# WIFI_Module.net
KiCad netlist of a schematic drawn in Altium Designer
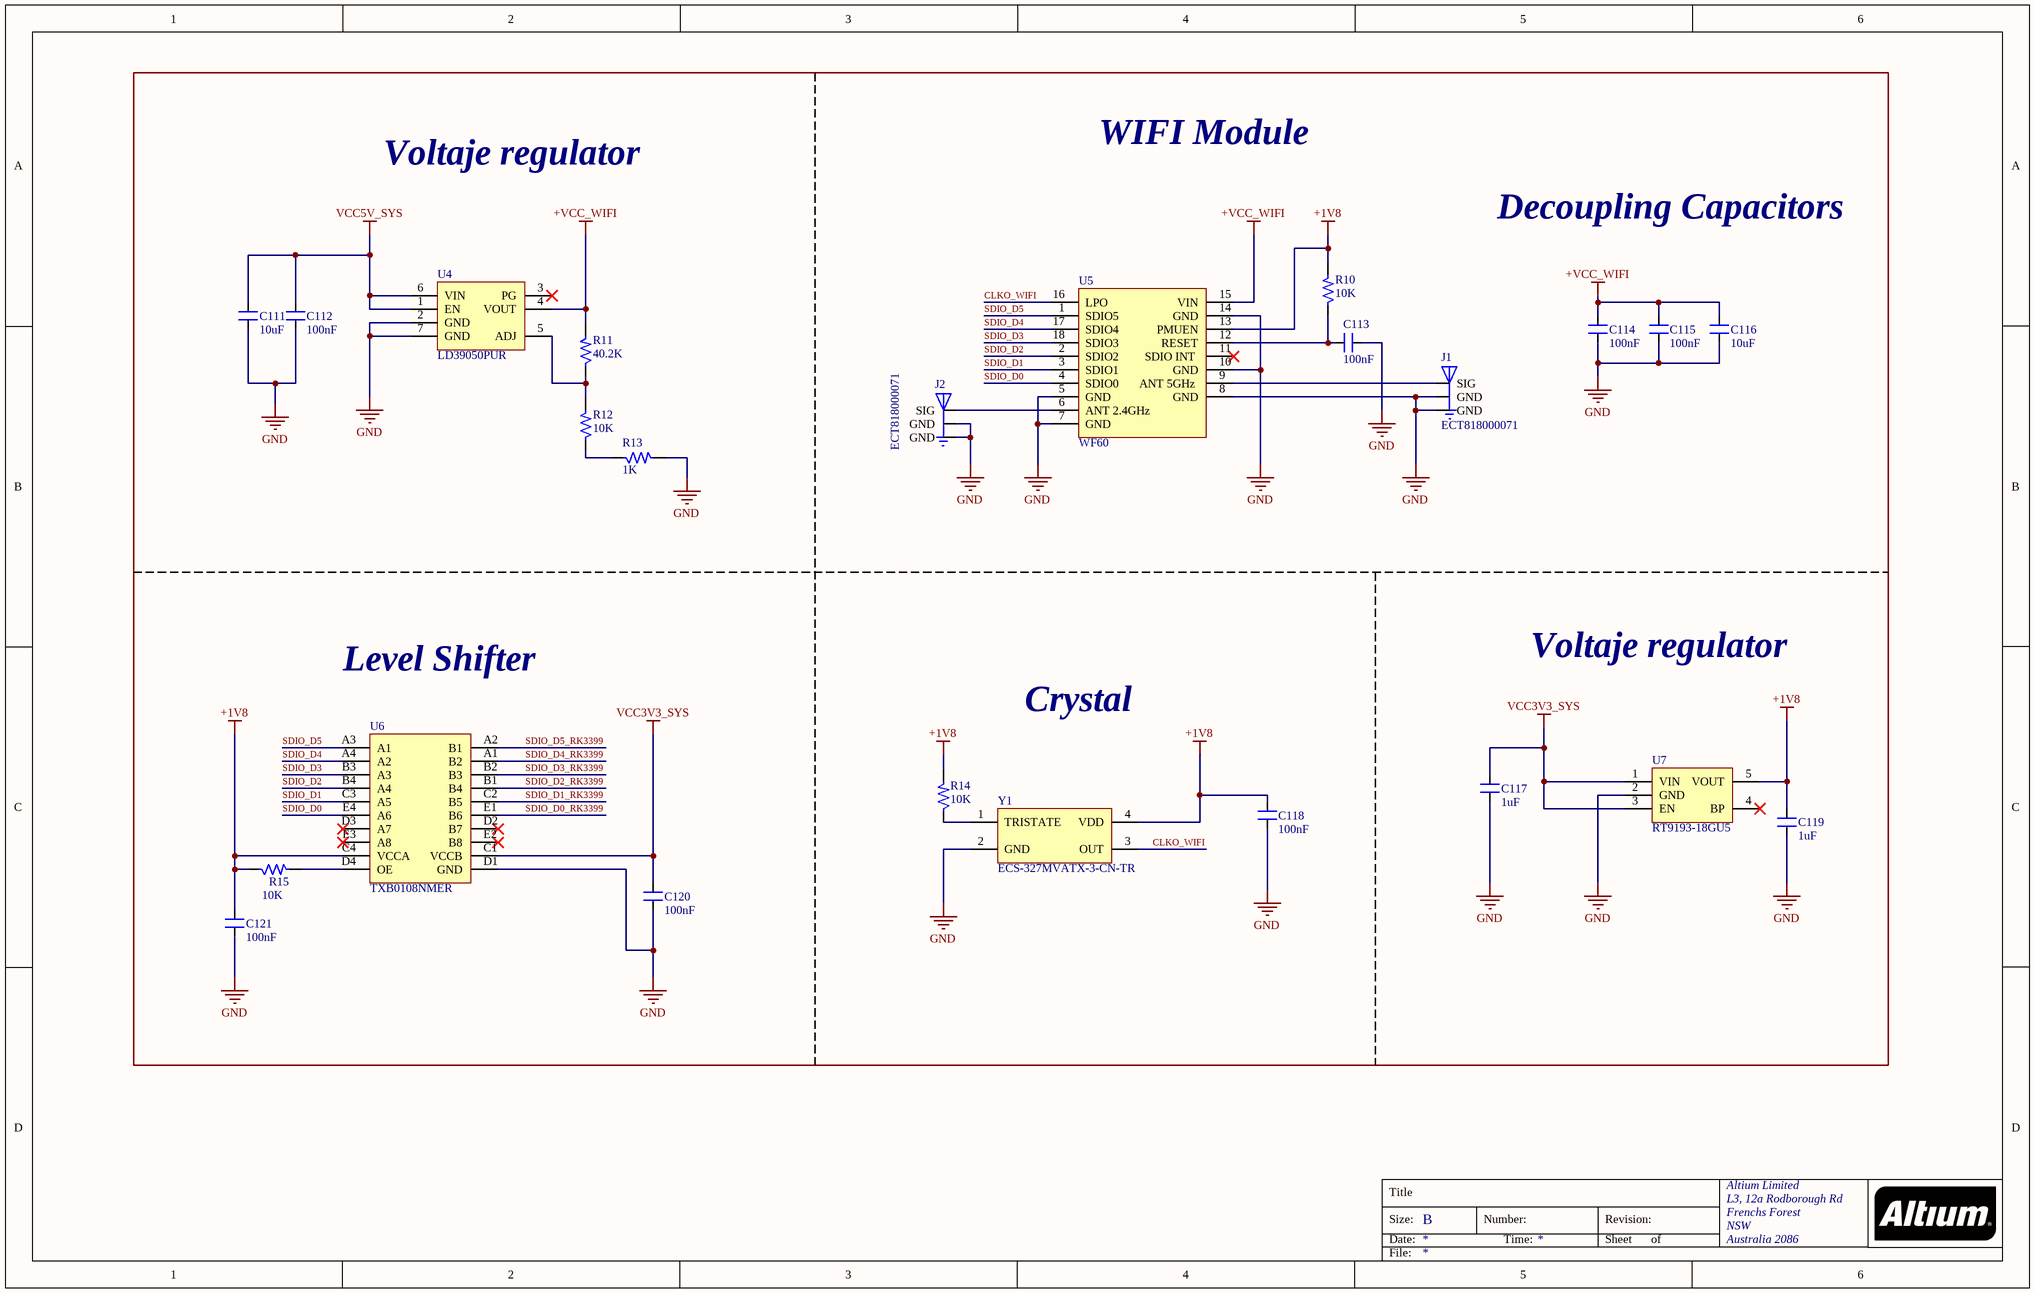
[diagram p0: WIFI_Module.SchDoc]

(export (version "E")
  (design (tool "Eeschema 10.0.6"))
  (components
    (comp (ref "C111")
      (value "10uF")
      (footprint "CAP_0603")
      (description "10µF ±10% 25V Ceramic Capacitor X5R 0603 (1608 Metric)")
      (fields
        (field (name "MANUFACTURER") "Murata Electronics")
        (field (name "MANUFACTURER PART NUMBER") "GRM188R61E106KA73D")
      )
      (libsource (lib "EsteemPCB_SOM_Course_intlib") (part "CAP_10uF-25V-10%-0603"))
    )
    (comp (ref "C112")
      (value "100nF")
      (footprint "CAP_0201")
      (description "0.1µF ±10% 25V Ceramic Capacitor X5R 0201 (0603 Metric)")
      (fields
        (field (name "MANUFACTURER") "TDK Corporation")
        (field (name "MANUFACTURER PART NUMBER") "C0603X5R1E104K030BB")
      )
      (libsource (lib "EsteemPCB_SOM_Course_intlib") (part "CAP_100nF-25V-10%-0201"))
    )
    (comp (ref "C113")
      (value "100nF")
      (footprint "CAP_0201")
      (description "0.1µF ±10% 25V Ceramic Capacitor X5R 0201 (0603 Metric)")
      (fields
        (field (name "MANUFACTURER") "TDK Corporation")
        (field (name "MANUFACTURER PART NUMBER") "C0603X5R1E104K030BB")
      )
      (libsource (lib "EsteemPCB_SOM_Course_intlib") (part "CAP_100nF-25V-10%-0201"))
    )
    (comp (ref "C114")
      (value "100nF")
      (footprint "CAP_0201")
      (description "0.1µF ±10% 25V Ceramic Capacitor X5R 0201 (0603 Metric)")
      (fields
        (field (name "MANUFACTURER") "TDK Corporation")
        (field (name "MANUFACTURER PART NUMBER") "C0603X5R1E104K030BB")
      )
      (libsource (lib "EsteemPCB_SOM_Course_intlib") (part "CAP_100nF-25V-10%-0201"))
    )
    (comp (ref "C115")
      (value "100nF")
      (footprint "CAP_0201")
      (description "0.1µF ±10% 25V Ceramic Capacitor X5R 0201 (0603 Metric)")
      (fields
        (field (name "MANUFACTURER") "TDK Corporation")
        (field (name "MANUFACTURER PART NUMBER") "C0603X5R1E104K030BB")
      )
      (libsource (lib "EsteemPCB_SOM_Course_intlib") (part "CAP_100nF-25V-10%-0201"))
    )
    (comp (ref "C116")
      (value "10uF")
      (footprint "CAP_0603")
      (description "10µF ±10% 25V Ceramic Capacitor X5R 0603 (1608 Metric)")
      (fields
        (field (name "MANUFACTURER") "Murata Electronics")
        (field (name "MANUFACTURER PART NUMBER") "GRM188R61E106KA73D")
      )
      (libsource (lib "EsteemPCB_SOM_Course_intlib") (part "CAP_10uF-25V-10%-0603"))
    )
    (comp (ref "C117")
      (value "1uF")
      (footprint "CAP_0201")
      (description "1µF ±20% 16V Ceramic Capacitor X5R 0201 (0603 Metric)")
      (fields
        (field (name "MANUFACTURER") "Samsung Electro-Mechanics")
        (field (name "MANUFACTURER PART NUMBER") "CL03A105MO3NRNH")
      )
      (libsource (lib "EsteemPCB_SOM_Course_intlib") (part "CAP_1uF-16V-10%-0201"))
    )
    (comp (ref "C118")
      (value "100nF")
      (footprint "CAP_0201")
      (description "0.1µF ±10% 25V Ceramic Capacitor X5R 0201 (0603 Metric)")
      (fields
        (field (name "MANUFACTURER") "TDK Corporation")
        (field (name "MANUFACTURER PART NUMBER") "C0603X5R1E104K030BB")
      )
      (libsource (lib "EsteemPCB_SOM_Course_intlib") (part "CAP_100nF-25V-10%-0201"))
    )
    (comp (ref "C119")
      (value "1uF")
      (footprint "CAP_0201")
      (description "1µF ±20% 16V Ceramic Capacitor X5R 0201 (0603 Metric)")
      (fields
        (field (name "MANUFACTURER") "Samsung Electro-Mechanics")
        (field (name "MANUFACTURER PART NUMBER") "CL03A105MO3NRNH")
      )
      (libsource (lib "EsteemPCB_SOM_Course_intlib") (part "CAP_1uF-16V-10%-0201"))
    )
    (comp (ref "C120")
      (value "100nF")
      (footprint "CAP_0201")
      (description "0.1µF ±10% 25V Ceramic Capacitor X5R 0201 (0603 Metric)")
      (fields
        (field (name "MANUFACTURER") "TDK Corporation")
        (field (name "MANUFACTURER PART NUMBER") "C0603X5R1E104K030BB")
      )
      (libsource (lib "EsteemPCB_SOM_Course_intlib") (part "CAP_100nF-25V-10%-0201"))
    )
    (comp (ref "C121")
      (value "100nF")
      (footprint "CAP_0201")
      (description "0.1µF ±10% 25V Ceramic Capacitor X5R 0201 (0603 Metric)")
      (fields
        (field (name "MANUFACTURER") "TDK Corporation")
        (field (name "MANUFACTURER PART NUMBER") "C0603X5R1E104K030BB")
      )
      (libsource (lib "EsteemPCB_SOM_Course_intlib") (part "CAP_100nF-25V-10%-0201"))
    )
    (comp (ref "J1")
      (value "ECT818000071")
      (footprint "CON3_UFL_116_SMD_ST")
      (description "SMD RF Connectors/Coaxial Connectors RoHS")
      (fields (field (name "MANUFACTURER") "ECT"))
      (libsource (lib "EsteemPCB_SOM_Course_intlib") (part "CON-PLG_3X1-ECT818000071-ST-SMD"))
    )
    (comp (ref "J2")
      (value "ECT818000071")
      (footprint "CON3_UFL_116_SMD_ST")
      (description "SMD RF Connectors/Coaxial Connectors RoHS")
      (fields (field (name "MANUFACTURER") "ECT"))
      (libsource (lib "EsteemPCB_SOM_Course_intlib") (part "CON-PLG_3X1-ECT818000071-ST-SMD"))
    )
    (comp (ref "R10")
      (value "10K")
      (footprint "RES_0201")
      (description "10 kOhms ±1% 0.05W, 1/20W Chip Resistor 0201 (0603 Metric) Thick Film")
      (fields
        (field (name "MANUFACTURER") "Stackpole Electronics Inc")
        (field (name "MANUFACTURER PART NUMBER") "RMCF0201FT10K0")
      )
      (libsource (lib "EsteemPCB_SOM_Course_intlib") (part "RES_10K-0.05W-1%-0201"))
    )
    (comp (ref "R11")
      (value "40.2K")
      (footprint "RES_0201")
      (fields
        (field (name "MANUFACTURER") "Yageo")
        (field (name "MANUFACTURER PART NUMBER") "AC0201FR-0740K2L")
      )
      (libsource (lib "EsteemPCB_SOM_Course_intlib") (part "RES_40.2K-0.05W-1%-0201"))
    )
    (comp (ref "R12")
      (value "10K")
      (footprint "RES_0201")
      (description "10 kOhms ±1% 0.05W, 1/20W Chip Resistor 0201 (0603 Metric) Thick Film")
      (fields
        (field (name "MANUFACTURER") "Stackpole Electronics Inc")
        (field (name "MANUFACTURER PART NUMBER") "RMCF0201FT10K0")
      )
      (libsource (lib "EsteemPCB_SOM_Course_intlib") (part "RES_10K-0.05W-1%-0201"))
    )
    (comp (ref "R13")
      (value "1K")
      (footprint "RES_0402")
      (description "1 kOhms ±1% 0.1W, 1/10W Chip Resistor 0402 (1005 Metric) Anti-Sulfur Thin Film")
      (fields
        (field (name "MANUFACTURER") "Vishay Beyschlag/Draloric/BC Components")
        (field (name "MANUFACTURER PART NUMBER") "MCS04020C1001FE000")
      )
      (libsource (lib "EsteemPCB_SOM_Course_intlib") (part "RES_1K-0.1W-1%-0402"))
    )
    (comp (ref "R14")
      (value "10K")
      (footprint "RES_0201")
      (description "10 kOhms ±1% 0.05W, 1/20W Chip Resistor 0201 (0603 Metric) Thick Film")
      (fields
        (field (name "MANUFACTURER") "Stackpole Electronics Inc")
        (field (name "MANUFACTURER PART NUMBER") "RMCF0201FT10K0")
      )
      (libsource (lib "EsteemPCB_SOM_Course_intlib") (part "RES_10K-0.05W-1%-0201"))
    )
    (comp (ref "R15")
      (value "10K")
      (footprint "RES_0201")
      (description "10 kOhms ±1% 0.05W, 1/20W Chip Resistor 0201 (0603 Metric) Thick Film")
      (fields
        (field (name "MANUFACTURER") "Stackpole Electronics Inc")
        (field (name "MANUFACTURER PART NUMBER") "RMCF0201FT10K0")
      )
      (libsource (lib "EsteemPCB_SOM_Course_intlib") (part "RES_10K-0.05W-1%-0201"))
    )
    (comp (ref "U4")
      (value "LD39050PUR")
      (footprint "DFN-6_37.4_165_33X15_SMD")
      (description "Adjustable 5.5V 0.8V 500mA DFN-6 Linear Voltage Regulators RoHS")
      (fields (field (name "MANUFACTURER") "STMicroelectronics"))
      (libsource (lib "EsteemPCB_SOM_Course_intlib") (part "REG_5.5V-0~5.1V-0.5A-2.55W-DFN-6"))
    )
    (comp (ref "U5")
      (value "WF60")
      (footprint "MOD_WF60")
      (description "Amp’ed RF Tech presents the WF60 WiFi dual\r\nband module: 802.11abgn.")
      (fields (field (name "MANUFACTURER") "Amp’ed"))
      (libsource (lib "EsteemPCB_SOM_Course_intlib") (part "MOD_WF60-SMD"))
    )
    (comp (ref "U6")
      (value "TXB0108NMER")
      (footprint "NFBGA_31.4_125.9X102.36")
      (fields (field (name "MANUFACTURER") "Texas Instruments"))
      (libsource (lib "EsteemPCB_SOM_Course_intlib") (part "IC_TXB0108NMER"))
    )
    (comp (ref "U7")
      (value "RT9193-18GU5")
      (footprint "SC70-5")
      (description "Linear Voltage Regulator IC 1 Output 300mA SC-70-5")
      (fields (field (name "MANUFACTURER") "Richtek USA Inc."))
      (libsource (lib "EsteemPCB_SOM_Course_intlib") (part "REG_1.8V-300mA-5.5V-SC70-5"))
    )
    (comp (ref "Y1")
      (value "ECS-327MVATX-3-CN-TR")
      (footprint "XTAL_57_35X31_SMD")
      (description "32.768kHz XO (Standard) CMOS Oscillator 1.6V ~ 3.6V Enable/Disable 4-SMD, No Lead")
      (fields (field (name "MANUFACTURER") "ECS INC"))
      (libsource (lib "EsteemPCB_SOM_Course_intlib") (part "XTAL_ECS-327MVATX-2-CN-TR"))
    )
  )
  (nets
    (net (code "1") (name "+1V8") (class "Default")
      (node (ref "C118") (pin "2") (pinfunction "2_2") (pintype "passive"))
      (node (ref "C119") (pin "2") (pinfunction "2_2") (pintype "passive"))
      (node (ref "C121") (pin "2") (pinfunction "2_2") (pintype "passive"))
      (node (ref "R10") (pin "2") (pinfunction "2_2") (pintype "passive"))
      (node (ref "R14") (pin "2") (pinfunction "2_2") (pintype "passive"))
      (node (ref "R15") (pin "1") (pinfunction "1_1") (pintype "passive"))
      (node (ref "U5") (pin "13") (pinfunction "PMUEN_13") (pintype "passive"))
      (node (ref "U6") (pin "C4") (pinfunction "VCCA_C4") (pintype "passive"))
      (node (ref "U7") (pin "5") (pinfunction "VOUT_5") (pintype "passive"))
      (node (ref "Y1") (pin "4") (pinfunction "VDD_4") (pintype "passive"))
    )
    (net (code "2") (name "+VCC_WIFI") (class "Default")
      (node (ref "C114") (pin "2") (pinfunction "2_2") (pintype "passive"))
      (node (ref "C115") (pin "2") (pinfunction "2_2") (pintype "passive"))
      (node (ref "C116") (pin "2") (pinfunction "2_2") (pintype "passive"))
      (node (ref "R11") (pin "2") (pinfunction "2_2") (pintype "passive"))
      (node (ref "U4") (pin "4") (pinfunction "VOUT_4") (pintype "passive"))
      (node (ref "U5") (pin "15") (pinfunction "VIN_15") (pintype "passive"))
    )
    (net (code "3") (name "/CLKO_WIFI") (class "Default")
      (node (ref "U5") (pin "16") (pinfunction "LPO_16") (pintype "passive"))
      (node (ref "Y1") (pin "3") (pinfunction "OUT_3") (pintype "passive"))
    )
    (net (code "4") (name "/SDIO_D0") (class "Default")
      (node (ref "U5") (pin "4") (pinfunction "SDIO0_4") (pintype "passive"))
      (node (ref "U6") (pin "E4") (pinfunction "A6_E4") (pintype "passive"))
    )
    (net (code "5") (name "/SDIO_D0_RK3399") (class "Default")
      (node (ref "U6") (pin "E1") (pinfunction "B6_E1") (pintype "passive"))
    )
    (net (code "6") (name "/SDIO_D1") (class "Default")
      (node (ref "U5") (pin "3") (pinfunction "SDIO1_3") (pintype "passive"))
      (node (ref "U6") (pin "C3") (pinfunction "A5_C3") (pintype "passive"))
    )
    (net (code "7") (name "/SDIO_D1_RK3399") (class "Default")
      (node (ref "U6") (pin "C2") (pinfunction "B5_C2") (pintype "passive"))
    )
    (net (code "8") (name "/SDIO_D2") (class "Default")
      (node (ref "U5") (pin "2") (pinfunction "SDIO2_2") (pintype "passive"))
      (node (ref "U6") (pin "B4") (pinfunction "A4_B4") (pintype "passive"))
    )
    (net (code "9") (name "/SDIO_D2_RK3399") (class "Default")
      (node (ref "U6") (pin "B1") (pinfunction "B4_B1") (pintype "passive"))
    )
    (net (code "10") (name "/SDIO_D3") (class "Default")
      (node (ref "U5") (pin "18") (pinfunction "SDIO3_18") (pintype "passive"))
      (node (ref "U6") (pin "B3") (pinfunction "A3_B3") (pintype "passive"))
    )
    (net (code "11") (name "/SDIO_D3_RK3399") (class "Default")
      (node (ref "U6") (pin "B2") (pinfunction "B3_B2") (pintype "passive"))
    )
    (net (code "12") (name "/SDIO_D4") (class "Default")
      (node (ref "U5") (pin "17") (pinfunction "SDIO4_17") (pintype "passive"))
      (node (ref "U6") (pin "A4") (pinfunction "A2_A4") (pintype "passive"))
    )
    (net (code "13") (name "/SDIO_D4_RK3399") (class "Default")
      (node (ref "U6") (pin "A1") (pinfunction "B2_A1") (pintype "passive"))
    )
    (net (code "14") (name "/SDIO_D5") (class "Default")
      (node (ref "U5") (pin "1") (pinfunction "SDIO5_1") (pintype "passive"))
      (node (ref "U6") (pin "A3") (pinfunction "A1_A3") (pintype "passive"))
    )
    (net (code "15") (name "/SDIO_D5_RK3399") (class "Default")
      (node (ref "U6") (pin "A2") (pinfunction "B1_A2") (pintype "passive"))
    )
    (net (code "16") (name "GND") (class "Default")
      (node (ref "C111") (pin "1") (pinfunction "1_1") (pintype "passive"))
      (node (ref "C112") (pin "1") (pinfunction "1_1") (pintype "passive"))
      (node (ref "C113") (pin "2") (pinfunction "2_2") (pintype "passive"))
      (node (ref "C114") (pin "1") (pinfunction "1_1") (pintype "passive"))
      (node (ref "C115") (pin "1") (pinfunction "1_1") (pintype "passive"))
      (node (ref "C116") (pin "1") (pinfunction "1_1") (pintype "passive"))
      (node (ref "C117") (pin "1") (pinfunction "1_1") (pintype "passive"))
      (node (ref "C118") (pin "1") (pinfunction "1_1") (pintype "passive"))
      (node (ref "C119") (pin "1") (pinfunction "1_1") (pintype "passive"))
      (node (ref "C120") (pin "1") (pinfunction "1_1") (pintype "passive"))
      (node (ref "C121") (pin "1") (pinfunction "1_1") (pintype "passive"))
      (node (ref "J1") (pin "1") (pinfunction "GND_1") (pintype "passive"))
      (node (ref "J1") (pin "3") (pinfunction "GND_3") (pintype "passive"))
      (node (ref "J2") (pin "1") (pinfunction "GND_1") (pintype "passive"))
      (node (ref "J2") (pin "3") (pinfunction "GND_3") (pintype "passive"))
      (node (ref "R13") (pin "2") (pinfunction "2_2") (pintype "passive"))
      (node (ref "U4") (pin "2") (pinfunction "GND_2") (pintype "passive"))
      (node (ref "U4") (pin "7") (pinfunction "GND_7") (pintype "passive"))
      (node (ref "U5") (pin "10") (pinfunction "GND_10") (pintype "passive"))
      (node (ref "U5") (pin "14") (pinfunction "GND_14") (pintype "passive"))
      (node (ref "U5") (pin "5") (pinfunction "GND_5") (pintype "passive"))
      (node (ref "U5") (pin "7") (pinfunction "GND_7") (pintype "passive"))
      (node (ref "U5") (pin "8") (pinfunction "GND_8") (pintype "passive"))
      (node (ref "U6") (pin "D1") (pinfunction "GND_D1") (pintype "passive"))
      (node (ref "U7") (pin "2") (pinfunction "GND_2") (pintype "passive"))
      (node (ref "Y1") (pin "2") (pinfunction "GND_2") (pintype "passive"))
    )
    (net (code "17") (name "Net-(J1-SIG)") (class "Default")
      (node (ref "J1") (pin "2") (pinfunction "SIG_2") (pintype "passive"))
      (node (ref "U5") (pin "9") (pinfunction "ANT_5GHz_9") (pintype "passive"))
    )
    (net (code "18") (name "Net-(J2-SIG)") (class "Default")
      (node (ref "J2") (pin "2") (pinfunction "SIG_2") (pintype "passive"))
      (node (ref "U5") (pin "6") (pinfunction "ANT_2.4GHz_6") (pintype "passive"))
    )
    (net (code "19") (name "Net-(R12-Pad1)") (class "Default")
      (node (ref "R12") (pin "1") (pinfunction "1_1") (pintype "passive"))
      (node (ref "R13") (pin "1") (pinfunction "1_1") (pintype "passive"))
    )
    (net (code "20") (name "Net-(U4-ADJ)") (class "Default")
      (node (ref "R11") (pin "1") (pinfunction "1_1") (pintype "passive"))
      (node (ref "R12") (pin "2") (pinfunction "2_2") (pintype "passive"))
      (node (ref "U4") (pin "5") (pinfunction "ADJ_5") (pintype "passive"))
    )
    (net (code "21") (name "Net-(U5-RESET)") (class "Default")
      (node (ref "C113") (pin "1") (pinfunction "1_1") (pintype "passive"))
      (node (ref "R10") (pin "1") (pinfunction "1_1") (pintype "passive"))
      (node (ref "U5") (pin "12") (pinfunction "RESET_12") (pintype "passive"))
    )
    (net (code "22") (name "Net-(U6-OE)") (class "Default")
      (node (ref "R15") (pin "2") (pinfunction "2_2") (pintype "passive"))
      (node (ref "U6") (pin "D4") (pinfunction "OE_D4") (pintype "passive"))
    )
    (net (code "23") (name "Net-(Y1-TRISTATE)") (class "Default")
      (node (ref "R14") (pin "1") (pinfunction "1_1") (pintype "passive"))
      (node (ref "Y1") (pin "1") (pinfunction "TRISTATE_1") (pintype "passive"))
    )
    (net (code "24") (name "VCC3V3_SYS") (class "Default")
      (node (ref "C117") (pin "2") (pinfunction "2_2") (pintype "passive"))
      (node (ref "C120") (pin "2") (pinfunction "2_2") (pintype "passive"))
      (node (ref "U6") (pin "C1") (pinfunction "VCCB_C1") (pintype "passive"))
      (node (ref "U7") (pin "1") (pinfunction "VIN_1") (pintype "passive"))
      (node (ref "U7") (pin "3") (pinfunction "EN_3") (pintype "passive"))
    )
    (net (code "25") (name "VCC5V_SYS") (class "Default")
      (node (ref "C111") (pin "2") (pinfunction "2_2") (pintype "passive"))
      (node (ref "C112") (pin "2") (pinfunction "2_2") (pintype "passive"))
      (node (ref "U4") (pin "1") (pinfunction "EN_1") (pintype "passive"))
      (node (ref "U4") (pin "6") (pinfunction "VIN_6") (pintype "passive"))
    )
    (net (code "26") (name "unconnected-(U4-PG-Pad3)") (class "Default")
      (node (ref "U4") (pin "3") (pinfunction "PG_3") (pintype "passive+no_connect"))
    )
    (net (code "27") (name "unconnected-(U5-SDIO_INT-Pad11)") (class "Default")
      (node (ref "U5") (pin "11") (pinfunction "SDIO_INT_11") (pintype "passive+no_connect"))
    )
    (net (code "28") (name "unconnected-(U6-A7-PadD3)") (class "Default")
      (node (ref "U6") (pin "D3") (pinfunction "A7_D3") (pintype "passive+no_connect"))
    )
    (net (code "29") (name "unconnected-(U6-A8-PadE3)") (class "Default")
      (node (ref "U6") (pin "E3") (pinfunction "A8_E3") (pintype "passive+no_connect"))
    )
    (net (code "30") (name "unconnected-(U6-B7-PadD2)") (class "Default")
      (node (ref "U6") (pin "D2") (pinfunction "B7_D2") (pintype "passive+no_connect"))
    )
    (net (code "31") (name "unconnected-(U6-B8-PadE2)") (class "Default")
      (node (ref "U6") (pin "E2") (pinfunction "B8_E2") (pintype "passive+no_connect"))
    )
    (net (code "32") (name "unconnected-(U7-BP-Pad4)") (class "Default")
      (node (ref "U7") (pin "4") (pinfunction "BP_4") (pintype "passive+no_connect"))
    )
  )
)
